# LCD_Board.net
KiCad netlist of a schematic drawn in Altium Designer
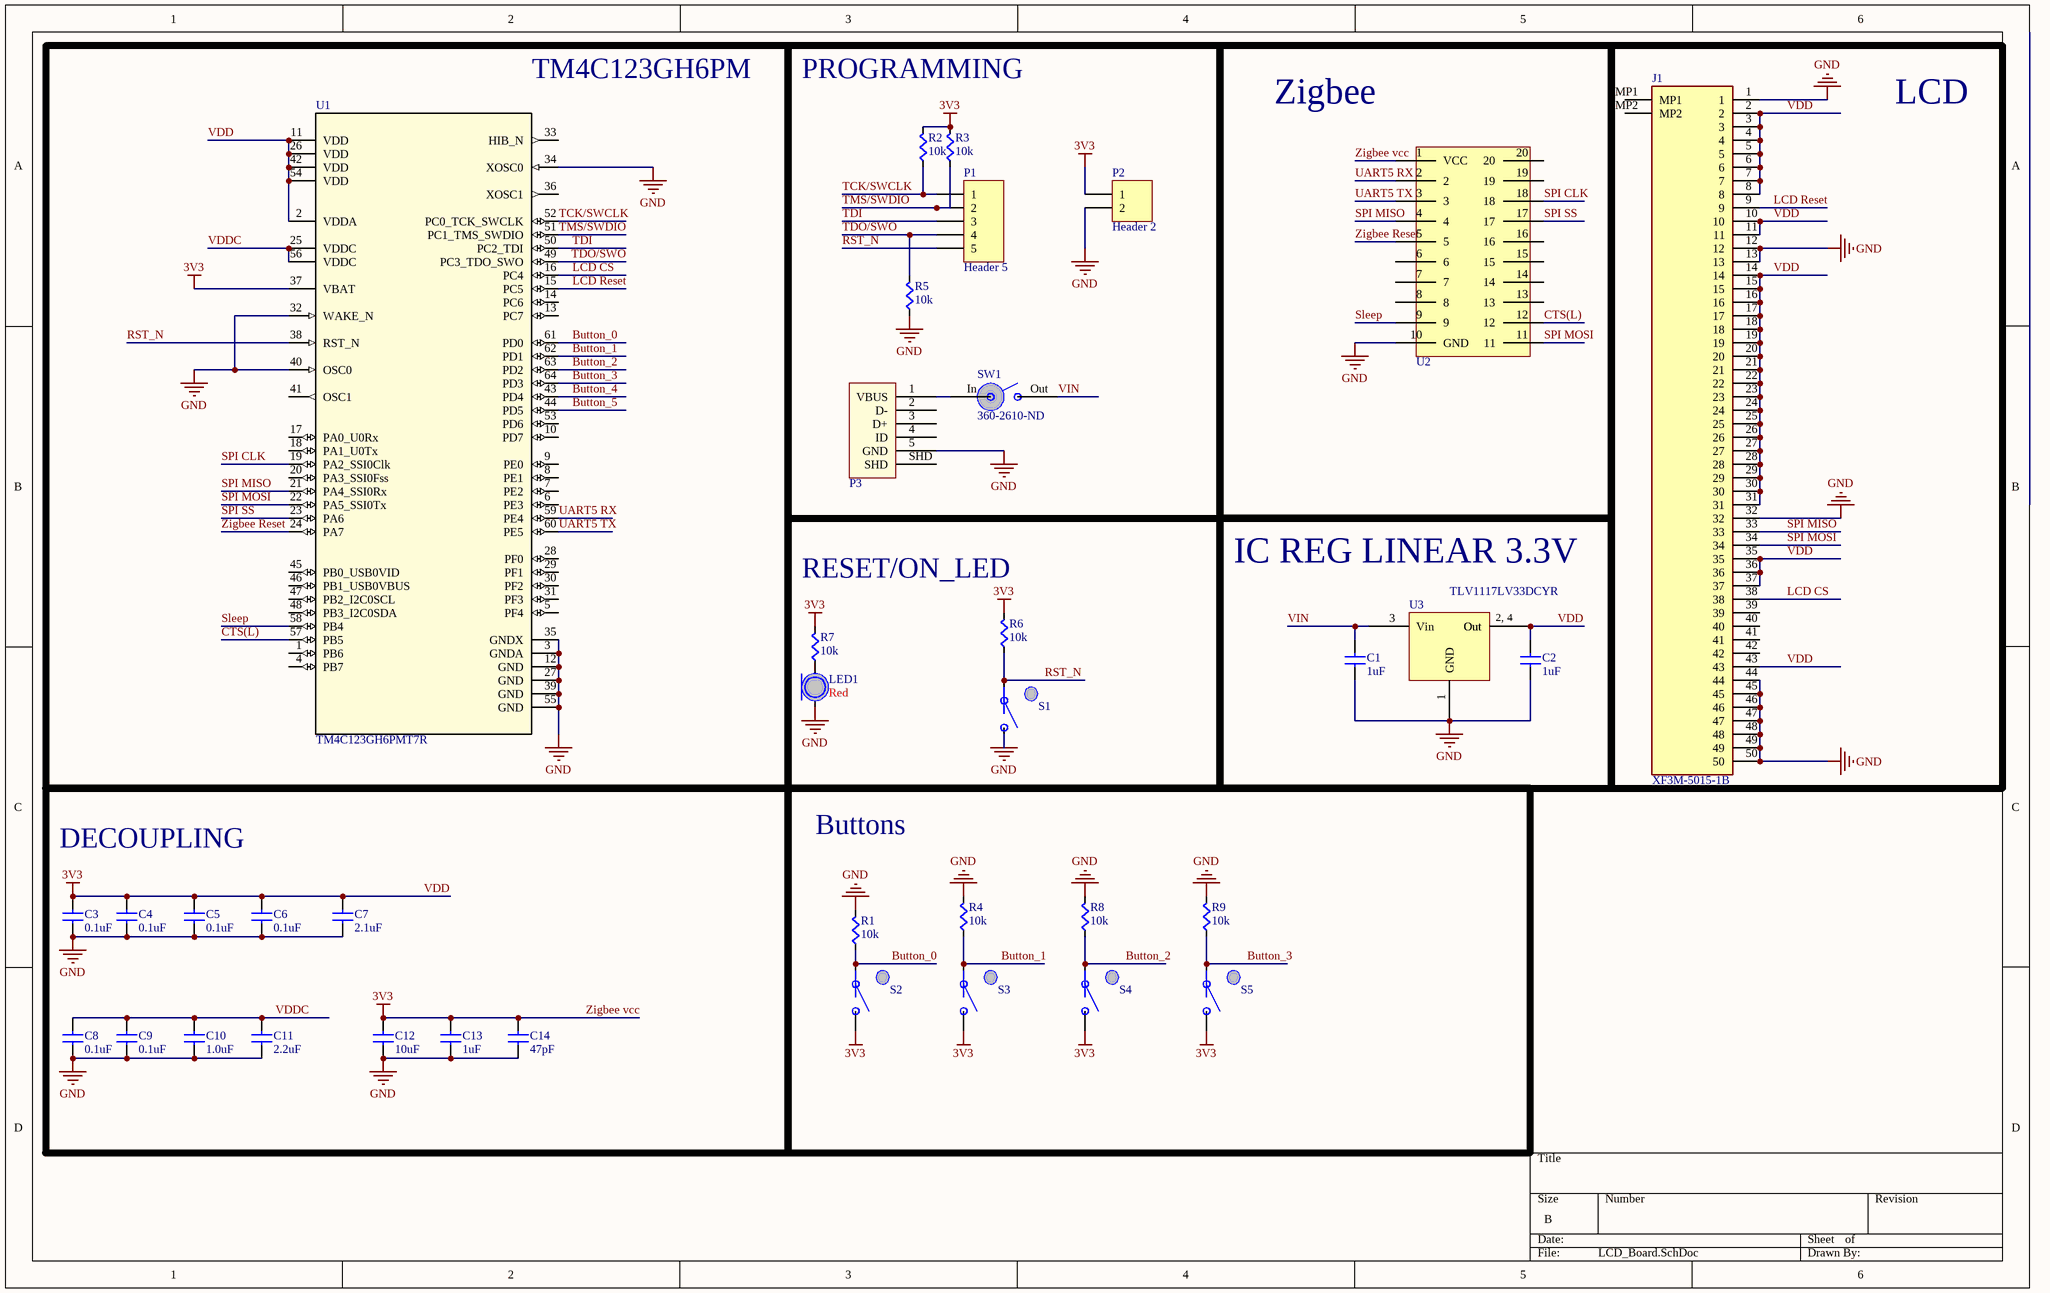
[diagram p0: LCD_Board.SchDoc]

(export (version "E")
  (design (tool "Eeschema 10.0.6"))
  (components
    (comp (ref "C1")
      (value "1uF")
      (footprint "CAPC0603")
      (fields (field (name "MANUFACTURER PART NUMBER") "C0603C105K8PACTU") (field (name "Comment") "Cap"))
      (libsource (lib "SubjuGator8") (part "Cap"))
    )
    (comp (ref "C2")
      (value "1uF")
      (footprint "CAPC0603")
      (fields (field (name "MANUFACTURER PART NUMBER") "C0603C105K8PACTU") (field (name "Comment") "Cap"))
      (libsource (lib "SubjuGator8") (part "Cap"))
    )
    (comp (ref "C3")
      (value "0.1uF")
      (footprint "CAPC0603")
      (fields (field (name "Comment") "Cap"))
      (libsource (lib "SubjuGator8") (part "Cap"))
    )
    (comp (ref "C4")
      (value "0.1uF")
      (footprint "CAPC0603")
      (fields (field (name "Comment") "Cap"))
      (libsource (lib "SubjuGator8") (part "Cap"))
    )
    (comp (ref "C5")
      (value "0.1uF")
      (footprint "CAPC0603")
      (fields (field (name "Comment") "Cap"))
      (libsource (lib "SubjuGator8") (part "Cap"))
    )
    (comp (ref "C6")
      (value "0.1uF")
      (footprint "CAPC0603")
      (fields (field (name "Comment") "Cap"))
      (libsource (lib "SubjuGator8") (part "Cap"))
    )
    (comp (ref "C7")
      (value "2.1uF")
      (footprint "CAPC0603")
      (fields (field (name "Comment") "Cap"))
      (libsource (lib "SubjuGator8") (part "Cap"))
    )
    (comp (ref "C8")
      (value "0.1uF")
      (footprint "CAPC0603")
      (fields (field (name "Comment") "Cap"))
      (libsource (lib "SubjuGator8") (part "Cap"))
    )
    (comp (ref "C9")
      (value "0.1uF")
      (footprint "CAPC0603")
      (fields (field (name "Comment") "Cap"))
      (libsource (lib "SubjuGator8") (part "Cap"))
    )
    (comp (ref "C10")
      (value "1.0uF")
      (footprint "CAPC0603")
      (fields (field (name "Comment") "Cap"))
      (libsource (lib "SubjuGator8") (part "Cap"))
    )
    (comp (ref "C11")
      (value "2.2uF")
      (footprint "CAPC0603")
      (fields (field (name "Comment") "Cap"))
      (libsource (lib "SubjuGator8") (part "Cap"))
    )
    (comp (ref "C12")
      (value "10uF")
      (footprint "CAPC0603")
      (fields (field (name "Comment") "Cap"))
      (libsource (lib "Passives") (part "Cap"))
    )
    (comp (ref "C13")
      (value "1uF")
      (footprint "CAPC0603")
      (fields (field (name "Comment") "Cap"))
      (libsource (lib "Passives") (part "Cap"))
    )
    (comp (ref "C14")
      (value "47pF")
      (footprint "CAPC0603")
      (fields (field (name "Comment") "Cap"))
      (libsource (lib "Passives") (part "Cap"))
    )
    (comp (ref "J1")
      (value "XF3M-5015-1B")
      (footprint "SamacSys:XF3M50151B")
      (description "Connector")
      (fields (field (name "MOUSER2 PART NUMBER") "653-XF3M-5015-1B"))
      (libsource (lib "*") (part "XF3M-5015-1B"))
    )
    (comp (ref "LED1")
      (value "LED")
      (footprint "LED0603")
      (fields (field (name "COLOR") "Red"))
      (libsource (lib "SubjuGator8") (part "LED"))
    )
    (comp (ref "P1")
      (value "Header 5")
      (footprint "HDR1X5")
      (description "Header, 5-Pin")
      (fields (field (name "PUBLISHER") "Altium Limited"))
      (libsource (lib "Miscellaneous Connectors") (part "Header 5"))
    )
    (comp (ref "P2")
      (value "Header 2")
      (footprint "HDR1X2")
      (description "Header, 2-Pin")
      (fields (field (name "PUBLISHER") "Altium Limited"))
      (libsource (lib "Miscellaneous Connectors") (part "Header 2"))
    )
    (comp (ref "P3")
      (value "USB Micro")
      (footprint "10118192-0001LF")
      (description "USB Mini B Metal Shield SMT")
      (libsource (lib "SubjuGator8") (part "USB Micro"))
    )
    (comp (ref "R1")
      (value "10k")
      (footprint "RES0603")
      (fields (field (name "Comment") "Res"))
      (libsource (lib "SubjuGator8") (part "Res"))
    )
    (comp (ref "R2")
      (value "10k")
      (footprint "RES0603")
      (fields (field (name "Comment") "Res"))
      (libsource (lib "SubjuGator8") (part "Res"))
    )
    (comp (ref "R3")
      (value "10k")
      (footprint "RES0603")
      (fields (field (name "Comment") "Res"))
      (libsource (lib "SubjuGator8") (part "Res"))
    )
    (comp (ref "R4")
      (value "10k")
      (footprint "RES0603")
      (fields (field (name "Comment") "Res"))
      (libsource (lib "SubjuGator8") (part "Res"))
    )
    (comp (ref "R5")
      (value "10k")
      (footprint "RES0603")
      (fields (field (name "Comment") "Res"))
      (libsource (lib "SubjuGator8") (part "Res"))
    )
    (comp (ref "R6")
      (value "10k")
      (footprint "RES0603")
      (fields (field (name "Comment") "Res"))
      (libsource (lib "SubjuGator8") (part "Res"))
    )
    (comp (ref "R7")
      (value "10k")
      (footprint "RES0603")
      (fields (field (name "Comment") "Res"))
      (libsource (lib "SubjuGator8") (part "Res"))
    )
    (comp (ref "R8")
      (value "10k")
      (footprint "RES0603")
      (fields (field (name "Comment") "Res"))
      (libsource (lib "SubjuGator8") (part "Res"))
    )
    (comp (ref "R9")
      (value "10k")
      (footprint "RES0603")
      (fields (field (name "Comment") "Res"))
      (libsource (lib "SubjuGator8") (part "Res"))
    )
    (comp (ref "S1")
      (value "Button")
      (footprint "PTS645xxxxSMTR92")
      (description "SPST Button")
      (libsource (lib "SubjuGator8") (part "Button"))
    )
    (comp (ref "S2")
      (value "Button")
      (footprint "PTS645xxxxSMTR92")
      (description "SPST Button")
      (libsource (lib "SubjuGator8") (part "Button"))
    )
    (comp (ref "S3")
      (value "Button")
      (footprint "PTS645xxxxSMTR92")
      (description "SPST Button")
      (libsource (lib "SubjuGator8") (part "Button"))
    )
    (comp (ref "S4")
      (value "Button")
      (footprint "PTS645xxxxSMTR92")
      (description "SPST Button")
      (libsource (lib "SubjuGator8") (part "Button"))
    )
    (comp (ref "S5")
      (value "Button")
      (footprint "PTS645xxxxSMTR92")
      (description "SPST Button")
      (libsource (lib "SubjuGator8") (part "Button"))
    )
    (comp (ref "SW1")
      (value "360-2610-ND")
      (footprint "AS11CP")
      (description "SPST Slide Switch")
      (libsource (lib "SubjuGator8") (part "SPST Slide Switch"))
    )
    (comp (ref "U1")
      (value "TM4C123GH6PMT7R")
      (footprint "PM0064A_N")
      (description "Imported")
      (fields
        (field (name "PARTNUMBER") "TM4C123GH6PMTR")
        (field (name "ALTERNATE_PARTNUMBER") "TM4C123GH6PMT")
      )
      (libsource (lib "TivaC") (part "TM4C123GH6PMT7R"))
    )
    (comp (ref "U2")
      (value "XBee")
      (footprint "XBee")
      (description "XBee radio")
      (libsource (lib "ICs") (part "XBee"))
    )
    (comp (ref "U3")
      (value "TLV1117LV33DCYR")
      (footprint "SOT23-4N")
      (description "IC REG LINEAR 3.3V 1A SOT223-4")
      (fields (field (name "DIGI-KEY PART NUMBER") "296-28778-1-ND"))
      (libsource (lib "ICs") (part "TLV1117LV33DCYR"))
    )
  )
  (nets
    (net (code "2") (name "/Button_0") (class "Default")
      (node (ref "R1") (pin "2") (pinfunction "B_2") (pintype "passive"))
      (node (ref "S2") (pin "A") (pinfunction "A_A") (pintype "passive"))
      (node (ref "U1") (pin "61") (pinfunction "PD0_61") (pintype "bidirectional"))
    )
    (net (code "3") (name "/Button_1") (class "Default")
      (node (ref "R4") (pin "2") (pinfunction "B_2") (pintype "passive"))
      (node (ref "S3") (pin "A") (pinfunction "A_A") (pintype "passive"))
      (node (ref "U1") (pin "62") (pinfunction "PD1_62") (pintype "bidirectional"))
    )
    (net (code "4") (name "/Button_2") (class "Default")
      (node (ref "R8") (pin "2") (pinfunction "B_2") (pintype "passive"))
      (node (ref "S4") (pin "A") (pinfunction "A_A") (pintype "passive"))
      (node (ref "U1") (pin "63") (pinfunction "PD2_63") (pintype "bidirectional"))
    )
    (net (code "5") (name "/Button_3") (class "Default")
      (node (ref "R9") (pin "2") (pinfunction "B_2") (pintype "passive"))
      (node (ref "S5") (pin "A") (pinfunction "A_A") (pintype "passive"))
      (node (ref "U1") (pin "64") (pinfunction "PD3_64") (pintype "bidirectional"))
    )
    (net (code "6") (name "/Button_4") (class "Default")
      (node (ref "U1") (pin "43") (pinfunction "PD4_43") (pintype "bidirectional"))
    )
    (net (code "7") (name "/Button_5") (class "Default")
      (node (ref "U1") (pin "44") (pinfunction "PD5_44") (pintype "bidirectional"))
    )
    (net (code "8") (name "/CTS(L)") (class "Default")
      (node (ref "U1") (pin "57") (pinfunction "PB5_57") (pintype "bidirectional"))
      (node (ref "U2") (pin "12") (pinfunction "12_12") (pintype "passive"))
    )
    (net (code "9") (name "/LCD CS") (class "Default")
      (node (ref "J1") (pin "38") (pinfunction "38_38") (pintype "passive"))
      (node (ref "U1") (pin "16") (pinfunction "PC4_16") (pintype "bidirectional"))
    )
    (net (code "10") (name "/LCD Reset") (class "Default")
      (node (ref "J1") (pin "9") (pinfunction "9_9") (pintype "passive"))
      (node (ref "U1") (pin "15") (pinfunction "PC5_15") (pintype "bidirectional"))
    )
    (net (code "11") (name "/RST_N") (class "Default")
      (node (ref "P1") (pin "5") (pinfunction "5_5") (pintype "passive"))
      (node (ref "R6") (pin "2") (pinfunction "B_2") (pintype "passive"))
      (node (ref "S1") (pin "A") (pinfunction "A_A") (pintype "passive"))
      (node (ref "U1") (pin "38") (pinfunction "RST_N_38") (pintype "input"))
    )
    (net (code "12") (name "/SPI CLK") (class "Default")
      (node (ref "U1") (pin "19") (pinfunction "PA2_SSI0Clk_19") (pintype "bidirectional"))
      (node (ref "U2") (pin "18") (pinfunction "18_18") (pintype "passive"))
    )
    (net (code "13") (name "/SPI MISO") (class "Default")
      (node (ref "J1") (pin "33") (pinfunction "33_33") (pintype "passive"))
      (node (ref "U1") (pin "21") (pinfunction "PA4_SSI0Rx_21") (pintype "bidirectional"))
      (node (ref "U2") (pin "4") (pinfunction "4_4") (pintype "passive"))
    )
    (net (code "14") (name "/SPI MOSI") (class "Default")
      (node (ref "J1") (pin "34") (pinfunction "34_34") (pintype "passive"))
      (node (ref "U1") (pin "22") (pinfunction "PA5_SSI0Tx_22") (pintype "bidirectional"))
      (node (ref "U2") (pin "11") (pinfunction "11_11") (pintype "passive"))
    )
    (net (code "15") (name "/SPI SS") (class "Default")
      (node (ref "U1") (pin "23") (pinfunction "PA6_23") (pintype "bidirectional"))
      (node (ref "U2") (pin "17") (pinfunction "17_17") (pintype "passive"))
    )
    (net (code "16") (name "/Sleep") (class "Default")
      (node (ref "U1") (pin "58") (pinfunction "PB4_58") (pintype "bidirectional"))
      (node (ref "U2") (pin "9") (pinfunction "9_9") (pintype "passive"))
    )
    (net (code "17") (name "/TCK{slash}SWCLK") (class "Default")
      (node (ref "P1") (pin "1") (pinfunction "1_1") (pintype "passive"))
      (node (ref "R2") (pin "2") (pinfunction "B_2") (pintype "passive"))
      (node (ref "U1") (pin "52") (pinfunction "PC0_TCK_SWCLK_52") (pintype "bidirectional"))
    )
    (net (code "18") (name "/TDI") (class "Default")
      (node (ref "P1") (pin "3") (pinfunction "3_3") (pintype "passive"))
      (node (ref "U1") (pin "50") (pinfunction "PC2_TDI_50") (pintype "bidirectional"))
    )
    (net (code "19") (name "/TDO{slash}SWO") (class "Default")
      (node (ref "P1") (pin "4") (pinfunction "4_4") (pintype "passive"))
      (node (ref "R5") (pin "1") (pinfunction "A_1") (pintype "passive"))
      (node (ref "U1") (pin "49") (pinfunction "PC3_TDO_SWO_49") (pintype "bidirectional"))
    )
    (net (code "20") (name "/TMS{slash}SWDIO") (class "Default")
      (node (ref "P1") (pin "2") (pinfunction "2_2") (pintype "passive"))
      (node (ref "R3") (pin "2") (pinfunction "B_2") (pintype "passive"))
      (node (ref "U1") (pin "51") (pinfunction "PC1_TMS_SWDIO_51") (pintype "bidirectional"))
    )
    (net (code "21") (name "/UART5 RX") (class "Default")
      (node (ref "U1") (pin "59") (pinfunction "PE4_59") (pintype "bidirectional"))
      (node (ref "U2") (pin "2") (pinfunction "2_2") (pintype "passive"))
    )
    (net (code "22") (name "/UART5 TX") (class "Default")
      (node (ref "U1") (pin "60") (pinfunction "PE5_60") (pintype "bidirectional"))
      (node (ref "U2") (pin "3") (pinfunction "3_3") (pintype "passive"))
    )
    (net (code "23") (name "/VDDC") (class "Default")
      (node (ref "C10") (pin "1") (pinfunction "A_1") (pintype "passive"))
      (node (ref "C11") (pin "1") (pinfunction "A_1") (pintype "passive"))
      (node (ref "C8") (pin "1") (pinfunction "A_1") (pintype "passive"))
      (node (ref "C9") (pin "1") (pinfunction "A_1") (pintype "passive"))
      (node (ref "U1") (pin "25") (pinfunction "VDDC_25") (pintype "power_in"))
      (node (ref "U1") (pin "56") (pinfunction "VDDC_56") (pintype "power_in"))
    )
    (net (code "24") (name "/VIN") (class "Default")
      (node (ref "C1") (pin "1") (pinfunction "A_1") (pintype "passive"))
      (node (ref "SW1") (pin "Out") (pinfunction "Out_Out") (pintype "passive"))
      (node (ref "U3") (pin "3") (pinfunction "Vin_3") (pintype "passive"))
    )
    (net (code "25") (name "/Zigbee Reset") (class "Default")
      (node (ref "U1") (pin "24") (pinfunction "PA7_24") (pintype "bidirectional"))
      (node (ref "U2") (pin "5") (pinfunction "5_5") (pintype "passive"))
    )
    (net (code "26") (name "3V3") (class "Default")
      (node (ref "C12") (pin "1") (pinfunction "A_1") (pintype "passive"))
      (node (ref "C13") (pin "1") (pinfunction "A_1") (pintype "passive"))
      (node (ref "C14") (pin "1") (pinfunction "A_1") (pintype "passive"))
      (node (ref "C2") (pin "1") (pinfunction "A_1") (pintype "passive"))
      (node (ref "C3") (pin "1") (pinfunction "A_1") (pintype "passive"))
      (node (ref "C4") (pin "1") (pinfunction "A_1") (pintype "passive"))
      (node (ref "C5") (pin "1") (pinfunction "A_1") (pintype "passive"))
      (node (ref "C6") (pin "1") (pinfunction "A_1") (pintype "passive"))
      (node (ref "C7") (pin "1") (pinfunction "A_1") (pintype "passive"))
      (node (ref "J1") (pin "10") (pinfunction "10_10") (pintype "passive"))
      (node (ref "J1") (pin "11") (pinfunction "11_11") (pintype "passive"))
      (node (ref "J1") (pin "14") (pinfunction "14_14") (pintype "passive"))
      (node (ref "J1") (pin "15") (pinfunction "15_15") (pintype "passive"))
      (node (ref "J1") (pin "16") (pinfunction "16_16") (pintype "passive"))
      (node (ref "J1") (pin "17") (pinfunction "17_17") (pintype "passive"))
      (node (ref "J1") (pin "18") (pinfunction "18_18") (pintype "passive"))
      (node (ref "J1") (pin "19") (pinfunction "19_19") (pintype "passive"))
      (node (ref "J1") (pin "2") (pinfunction "2_2") (pintype "passive"))
      (node (ref "J1") (pin "20") (pinfunction "20_20") (pintype "passive"))
      (node (ref "J1") (pin "21") (pinfunction "21_21") (pintype "passive"))
      (node (ref "J1") (pin "22") (pinfunction "22_22") (pintype "passive"))
      (node (ref "J1") (pin "23") (pinfunction "23_23") (pintype "passive"))
      (node (ref "J1") (pin "24") (pinfunction "24_24") (pintype "passive"))
      (node (ref "J1") (pin "25") (pinfunction "25_25") (pintype "passive"))
      (node (ref "J1") (pin "26") (pinfunction "26_26") (pintype "passive"))
      (node (ref "J1") (pin "27") (pinfunction "27_27") (pintype "passive"))
      (node (ref "J1") (pin "28") (pinfunction "28_28") (pintype "passive"))
      (node (ref "J1") (pin "29") (pinfunction "29_29") (pintype "passive"))
      (node (ref "J1") (pin "3") (pinfunction "3_3") (pintype "passive"))
      (node (ref "J1") (pin "30") (pinfunction "30_30") (pintype "passive"))
      (node (ref "J1") (pin "31") (pinfunction "31_31") (pintype "passive"))
      (node (ref "J1") (pin "35") (pinfunction "35_35") (pintype "passive"))
      (node (ref "J1") (pin "36") (pinfunction "36_36") (pintype "passive"))
      (node (ref "J1") (pin "37") (pinfunction "37_37") (pintype "passive"))
      (node (ref "J1") (pin "4") (pinfunction "4_4") (pintype "passive"))
      (node (ref "J1") (pin "43") (pinfunction "43_43") (pintype "passive"))
      (node (ref "J1") (pin "5") (pinfunction "5_5") (pintype "passive"))
      (node (ref "J1") (pin "6") (pinfunction "6_6") (pintype "passive"))
      (node (ref "J1") (pin "7") (pinfunction "7_7") (pintype "passive"))
      (node (ref "J1") (pin "8") (pinfunction "8_8") (pintype "passive"))
      (node (ref "P2") (pin "1") (pinfunction "1_1") (pintype "passive"))
      (node (ref "R2") (pin "1") (pinfunction "A_1") (pintype "passive"))
      (node (ref "R3") (pin "1") (pinfunction "A_1") (pintype "passive"))
      (node (ref "R6") (pin "1") (pinfunction "A_1") (pintype "passive"))
      (node (ref "R7") (pin "1") (pinfunction "A_1") (pintype "passive"))
      (node (ref "S2") (pin "B") (pinfunction "B_B") (pintype "passive"))
      (node (ref "S3") (pin "B") (pinfunction "B_B") (pintype "passive"))
      (node (ref "S4") (pin "B") (pinfunction "B_B") (pintype "passive"))
      (node (ref "S5") (pin "B") (pinfunction "B_B") (pintype "passive"))
      (node (ref "U1") (pin "11") (pinfunction "VDD_11") (pintype "power_in"))
      (node (ref "U1") (pin "2") (pinfunction "VDDA_2") (pintype "power_in"))
      (node (ref "U1") (pin "26") (pinfunction "VDD_26") (pintype "power_in"))
      (node (ref "U1") (pin "37") (pinfunction "VBAT_37") (pintype "power_in"))
      (node (ref "U1") (pin "42") (pinfunction "VDD_42") (pintype "power_in"))
      (node (ref "U1") (pin "54") (pinfunction "VDD_54") (pintype "power_in"))
      (node (ref "U2") (pin "1") (pinfunction "VCC_1") (pintype "passive"))
      (node (ref "U3") (pin "2") (pinfunction "Out_2") (pintype "passive"))
      (node (ref "U3") (pin "4") (pinfunction "Out_4") (pintype "passive"))
    )
    (net (code "27") (name "GND") (class "Default")
      (node (ref "C1") (pin "2") (pinfunction "B_2") (pintype "passive"))
      (node (ref "C10") (pin "2") (pinfunction "B_2") (pintype "passive"))
      (node (ref "C11") (pin "2") (pinfunction "B_2") (pintype "passive"))
      (node (ref "C12") (pin "2") (pinfunction "B_2") (pintype "passive"))
      (node (ref "C13") (pin "2") (pinfunction "B_2") (pintype "passive"))
      (node (ref "C14") (pin "2") (pinfunction "B_2") (pintype "passive"))
      (node (ref "C2") (pin "2") (pinfunction "B_2") (pintype "passive"))
      (node (ref "C3") (pin "2") (pinfunction "B_2") (pintype "passive"))
      (node (ref "C4") (pin "2") (pinfunction "B_2") (pintype "passive"))
      (node (ref "C5") (pin "2") (pinfunction "B_2") (pintype "passive"))
      (node (ref "C6") (pin "2") (pinfunction "B_2") (pintype "passive"))
      (node (ref "C7") (pin "2") (pinfunction "B_2") (pintype "passive"))
      (node (ref "C8") (pin "2") (pinfunction "B_2") (pintype "passive"))
      (node (ref "C9") (pin "2") (pinfunction "B_2") (pintype "passive"))
      (node (ref "J1") (pin "1") (pinfunction "1_1") (pintype "passive"))
      (node (ref "J1") (pin "12") (pinfunction "12_12") (pintype "passive"))
      (node (ref "J1") (pin "13") (pinfunction "13_13") (pintype "passive"))
      (node (ref "J1") (pin "32") (pinfunction "32_32") (pintype "passive"))
      (node (ref "J1") (pin "44") (pinfunction "44_44") (pintype "passive"))
      (node (ref "J1") (pin "45") (pinfunction "45_45") (pintype "passive"))
      (node (ref "J1") (pin "46") (pinfunction "46_46") (pintype "passive"))
      (node (ref "J1") (pin "47") (pinfunction "47_47") (pintype "passive"))
      (node (ref "J1") (pin "48") (pinfunction "48_48") (pintype "passive"))
      (node (ref "J1") (pin "49") (pinfunction "49_49") (pintype "passive"))
      (node (ref "J1") (pin "50") (pinfunction "50_50") (pintype "passive"))
      (node (ref "LED1") (pin "C") (pinfunction "C_C") (pintype "passive"))
      (node (ref "P2") (pin "2") (pinfunction "2_2") (pintype "passive"))
      (node (ref "P3") (pin "5") (pinfunction "GND_5") (pintype "passive"))
      (node (ref "R1") (pin "1") (pinfunction "A_1") (pintype "passive"))
      (node (ref "R4") (pin "1") (pinfunction "A_1") (pintype "passive"))
      (node (ref "R5") (pin "2") (pinfunction "B_2") (pintype "passive"))
      (node (ref "R8") (pin "1") (pinfunction "A_1") (pintype "passive"))
      (node (ref "R9") (pin "1") (pinfunction "A_1") (pintype "passive"))
      (node (ref "S1") (pin "B") (pinfunction "B_B") (pintype "passive"))
      (node (ref "U1") (pin "12") (pinfunction "GND_12") (pintype "power_in"))
      (node (ref "U1") (pin "27") (pinfunction "GND_27") (pintype "power_in"))
      (node (ref "U1") (pin "3") (pinfunction "GNDA_3") (pintype "power_in"))
      (node (ref "U1") (pin "32") (pinfunction "WAKE_N_32") (pintype "input"))
      (node (ref "U1") (pin "34") (pinfunction "XOSC0_34") (pintype "input"))
      (node (ref "U1") (pin "35") (pinfunction "GNDX_35") (pintype "power_in"))
      (node (ref "U1") (pin "39") (pinfunction "GND_39") (pintype "power_in"))
      (node (ref "U1") (pin "40") (pinfunction "OSC0_40") (pintype "input"))
      (node (ref "U1") (pin "55") (pinfunction "GND_55") (pintype "power_in"))
      (node (ref "U2") (pin "10") (pinfunction "GND_10") (pintype "passive"))
      (node (ref "U3") (pin "1") (pinfunction "GND_1") (pintype "passive"))
    )
    (net (code "28") (name "Net-(P3-VBUS)") (class "Default")
      (node (ref "P3") (pin "1") (pinfunction "VBUS_1") (pintype "passive"))
      (node (ref "SW1") (pin "In") (pinfunction "In_In") (pintype "passive"))
    )
    (net (code "29") (name "Net-(R7-B)") (class "Default")
      (node (ref "LED1") (pin "A") (pinfunction "A_A") (pintype "passive"))
      (node (ref "R7") (pin "2") (pinfunction "B_2") (pintype "passive"))
    )
    (net (code "30") (name "unconnected-(J1-Pad39)") (class "Default")
      (node (ref "J1") (pin "39") (pinfunction "39_39") (pintype "passive"))
    )
    (net (code "31") (name "unconnected-(J1-Pad40)") (class "Default")
      (node (ref "J1") (pin "40") (pinfunction "40_40") (pintype "passive"))
    )
    (net (code "32") (name "unconnected-(J1-Pad41)") (class "Default")
      (node (ref "J1") (pin "41") (pinfunction "41_41") (pintype "passive"))
    )
    (net (code "33") (name "unconnected-(J1-Pad42)") (class "Default")
      (node (ref "J1") (pin "42") (pinfunction "42_42") (pintype "passive"))
    )
    (net (code "34") (name "unconnected-(J1-PadMP1)") (class "Default")
      (node (ref "J1") (pin "MP1") (pinfunction "MP1_MP1") (pintype "passive"))
    )
    (net (code "35") (name "unconnected-(J1-PadMP2)") (class "Default")
      (node (ref "J1") (pin "MP2") (pinfunction "MP2_MP2") (pintype "passive"))
    )
    (net (code "36") (name "unconnected-(P3-D+-Pad3)") (class "Default")
      (node (ref "P3") (pin "3") (pinfunction "D+_3") (pintype "passive"))
    )
    (net (code "37") (name "unconnected-(P3-D--Pad2)") (class "Default")
      (node (ref "P3") (pin "2") (pinfunction "D-_2") (pintype "passive"))
    )
    (net (code "38") (name "unconnected-(P3-ID-Pad4)") (class "Default")
      (node (ref "P3") (pin "4") (pinfunction "ID_4") (pintype "passive"))
    )
    (net (code "39") (name "unconnected-(P3-PadSHD)") (class "Default")
      (node (ref "P3") (pin "SHD") (pinfunction "SHD_SHD") (pintype "passive"))
    )
    (net (code "40") (name "unconnected-(U1-HIB_N-Pad33)") (class "Default")
      (node (ref "U1") (pin "33") (pinfunction "HIB_N_33") (pintype "output"))
    )
    (net (code "41") (name "unconnected-(U1-OSC1-Pad41)") (class "Default")
      (node (ref "U1") (pin "41") (pinfunction "OSC1_41") (pintype "output"))
    )
    (net (code "42") (name "unconnected-(U1-PA0_U0Rx-Pad17)") (class "Default")
      (node (ref "U1") (pin "17") (pinfunction "PA0_U0Rx_17") (pintype "bidirectional"))
    )
    (net (code "43") (name "unconnected-(U1-PA1_U0Tx-Pad18)") (class "Default")
      (node (ref "U1") (pin "18") (pinfunction "PA1_U0Tx_18") (pintype "bidirectional"))
    )
    (net (code "44") (name "unconnected-(U1-PA3_SSI0Fss-Pad20)") (class "Default")
      (node (ref "U1") (pin "20") (pinfunction "PA3_SSI0Fss_20") (pintype "bidirectional"))
    )
    (net (code "45") (name "unconnected-(U1-PB0_USB0VID-Pad45)") (class "Default")
      (node (ref "U1") (pin "45") (pinfunction "PB0_USB0VID_45") (pintype "bidirectional"))
    )
    (net (code "46") (name "unconnected-(U1-PB1_USB0VBUS-Pad46)") (class "Default")
      (node (ref "U1") (pin "46") (pinfunction "PB1_USB0VBUS_46") (pintype "bidirectional"))
    )
    (net (code "47") (name "unconnected-(U1-PB2_I2C0SCL-Pad47)") (class "Default")
      (node (ref "U1") (pin "47") (pinfunction "PB2_I2C0SCL_47") (pintype "bidirectional"))
    )
    (net (code "48") (name "unconnected-(U1-PB3_I2C0SDA-Pad48)") (class "Default")
      (node (ref "U1") (pin "48") (pinfunction "PB3_I2C0SDA_48") (pintype "bidirectional"))
    )
    (net (code "49") (name "unconnected-(U1-PB6-Pad1)") (class "Default")
      (node (ref "U1") (pin "1") (pinfunction "PB6_1") (pintype "bidirectional"))
    )
    (net (code "50") (name "unconnected-(U1-PB7-Pad4)") (class "Default")
      (node (ref "U1") (pin "4") (pinfunction "PB7_4") (pintype "bidirectional"))
    )
    (net (code "51") (name "unconnected-(U1-PC6-Pad14)") (class "Default")
      (node (ref "U1") (pin "14") (pinfunction "PC6_14") (pintype "bidirectional"))
    )
    (net (code "52") (name "unconnected-(U1-PC7-Pad13)") (class "Default")
      (node (ref "U1") (pin "13") (pinfunction "PC7_13") (pintype "bidirectional"))
    )
    (net (code "53") (name "unconnected-(U1-PD6-Pad53)") (class "Default")
      (node (ref "U1") (pin "53") (pinfunction "PD6_53") (pintype "bidirectional"))
    )
    (net (code "54") (name "unconnected-(U1-PD7-Pad10)") (class "Default")
      (node (ref "U1") (pin "10") (pinfunction "PD7_10") (pintype "bidirectional"))
    )
    (net (code "55") (name "unconnected-(U1-PE0-Pad9)") (class "Default")
      (node (ref "U1") (pin "9") (pinfunction "PE0_9") (pintype "bidirectional"))
    )
    (net (code "56") (name "unconnected-(U1-PE1-Pad8)") (class "Default")
      (node (ref "U1") (pin "8") (pinfunction "PE1_8") (pintype "bidirectional"))
    )
    (net (code "57") (name "unconnected-(U1-PE2-Pad7)") (class "Default")
      (node (ref "U1") (pin "7") (pinfunction "PE2_7") (pintype "bidirectional"))
    )
    (net (code "58") (name "unconnected-(U1-PE3-Pad6)") (class "Default")
      (node (ref "U1") (pin "6") (pinfunction "PE3_6") (pintype "bidirectional"))
    )
    (net (code "59") (name "unconnected-(U1-PF0-Pad28)") (class "Default")
      (node (ref "U1") (pin "28") (pinfunction "PF0_28") (pintype "bidirectional"))
    )
    (net (code "60") (name "unconnected-(U1-PF1-Pad29)") (class "Default")
      (node (ref "U1") (pin "29") (pinfunction "PF1_29") (pintype "bidirectional"))
    )
    (net (code "61") (name "unconnected-(U1-PF2-Pad30)") (class "Default")
      (node (ref "U1") (pin "30") (pinfunction "PF2_30") (pintype "bidirectional"))
    )
    (net (code "62") (name "unconnected-(U1-PF3-Pad31)") (class "Default")
      (node (ref "U1") (pin "31") (pinfunction "PF3_31") (pintype "bidirectional"))
    )
    (net (code "63") (name "unconnected-(U1-PF4-Pad5)") (class "Default")
      (node (ref "U1") (pin "5") (pinfunction "PF4_5") (pintype "bidirectional"))
    )
    (net (code "64") (name "unconnected-(U1-XOSC1-Pad36)") (class "Default")
      (node (ref "U1") (pin "36") (pinfunction "XOSC1_36") (pintype "output"))
    )
    (net (code "65") (name "unconnected-(U2-Pad6)") (class "Default")
      (node (ref "U2") (pin "6") (pinfunction "6_6") (pintype "passive"))
    )
    (net (code "66") (name "unconnected-(U2-Pad7)") (class "Default")
      (node (ref "U2") (pin "7") (pinfunction "7_7") (pintype "passive"))
    )
    (net (code "67") (name "unconnected-(U2-Pad8)") (class "Default")
      (node (ref "U2") (pin "8") (pinfunction "8_8") (pintype "passive"))
    )
    (net (code "68") (name "unconnected-(U2-Pad13)") (class "Default")
      (node (ref "U2") (pin "13") (pinfunction "13_13") (pintype "passive"))
    )
    (net (code "69") (name "unconnected-(U2-Pad14)") (class "Default")
      (node (ref "U2") (pin "14") (pinfunction "14_14") (pintype "passive"))
    )
    (net (code "70") (name "unconnected-(U2-Pad15)") (class "Default")
      (node (ref "U2") (pin "15") (pinfunction "15_15") (pintype "passive"))
    )
    (net (code "71") (name "unconnected-(U2-Pad16)") (class "Default")
      (node (ref "U2") (pin "16") (pinfunction "16_16") (pintype "passive"))
    )
    (net (code "72") (name "unconnected-(U2-Pad19)") (class "Default")
      (node (ref "U2") (pin "19") (pinfunction "19_19") (pintype "passive"))
    )
    (net (code "73") (name "unconnected-(U2-Pad20)") (class "Default")
      (node (ref "U2") (pin "20") (pinfunction "20_20") (pintype "passive"))
    )
  )
)
